# blackbox_sch.net
KiCad netlist of a schematic drawn in Altium Designer
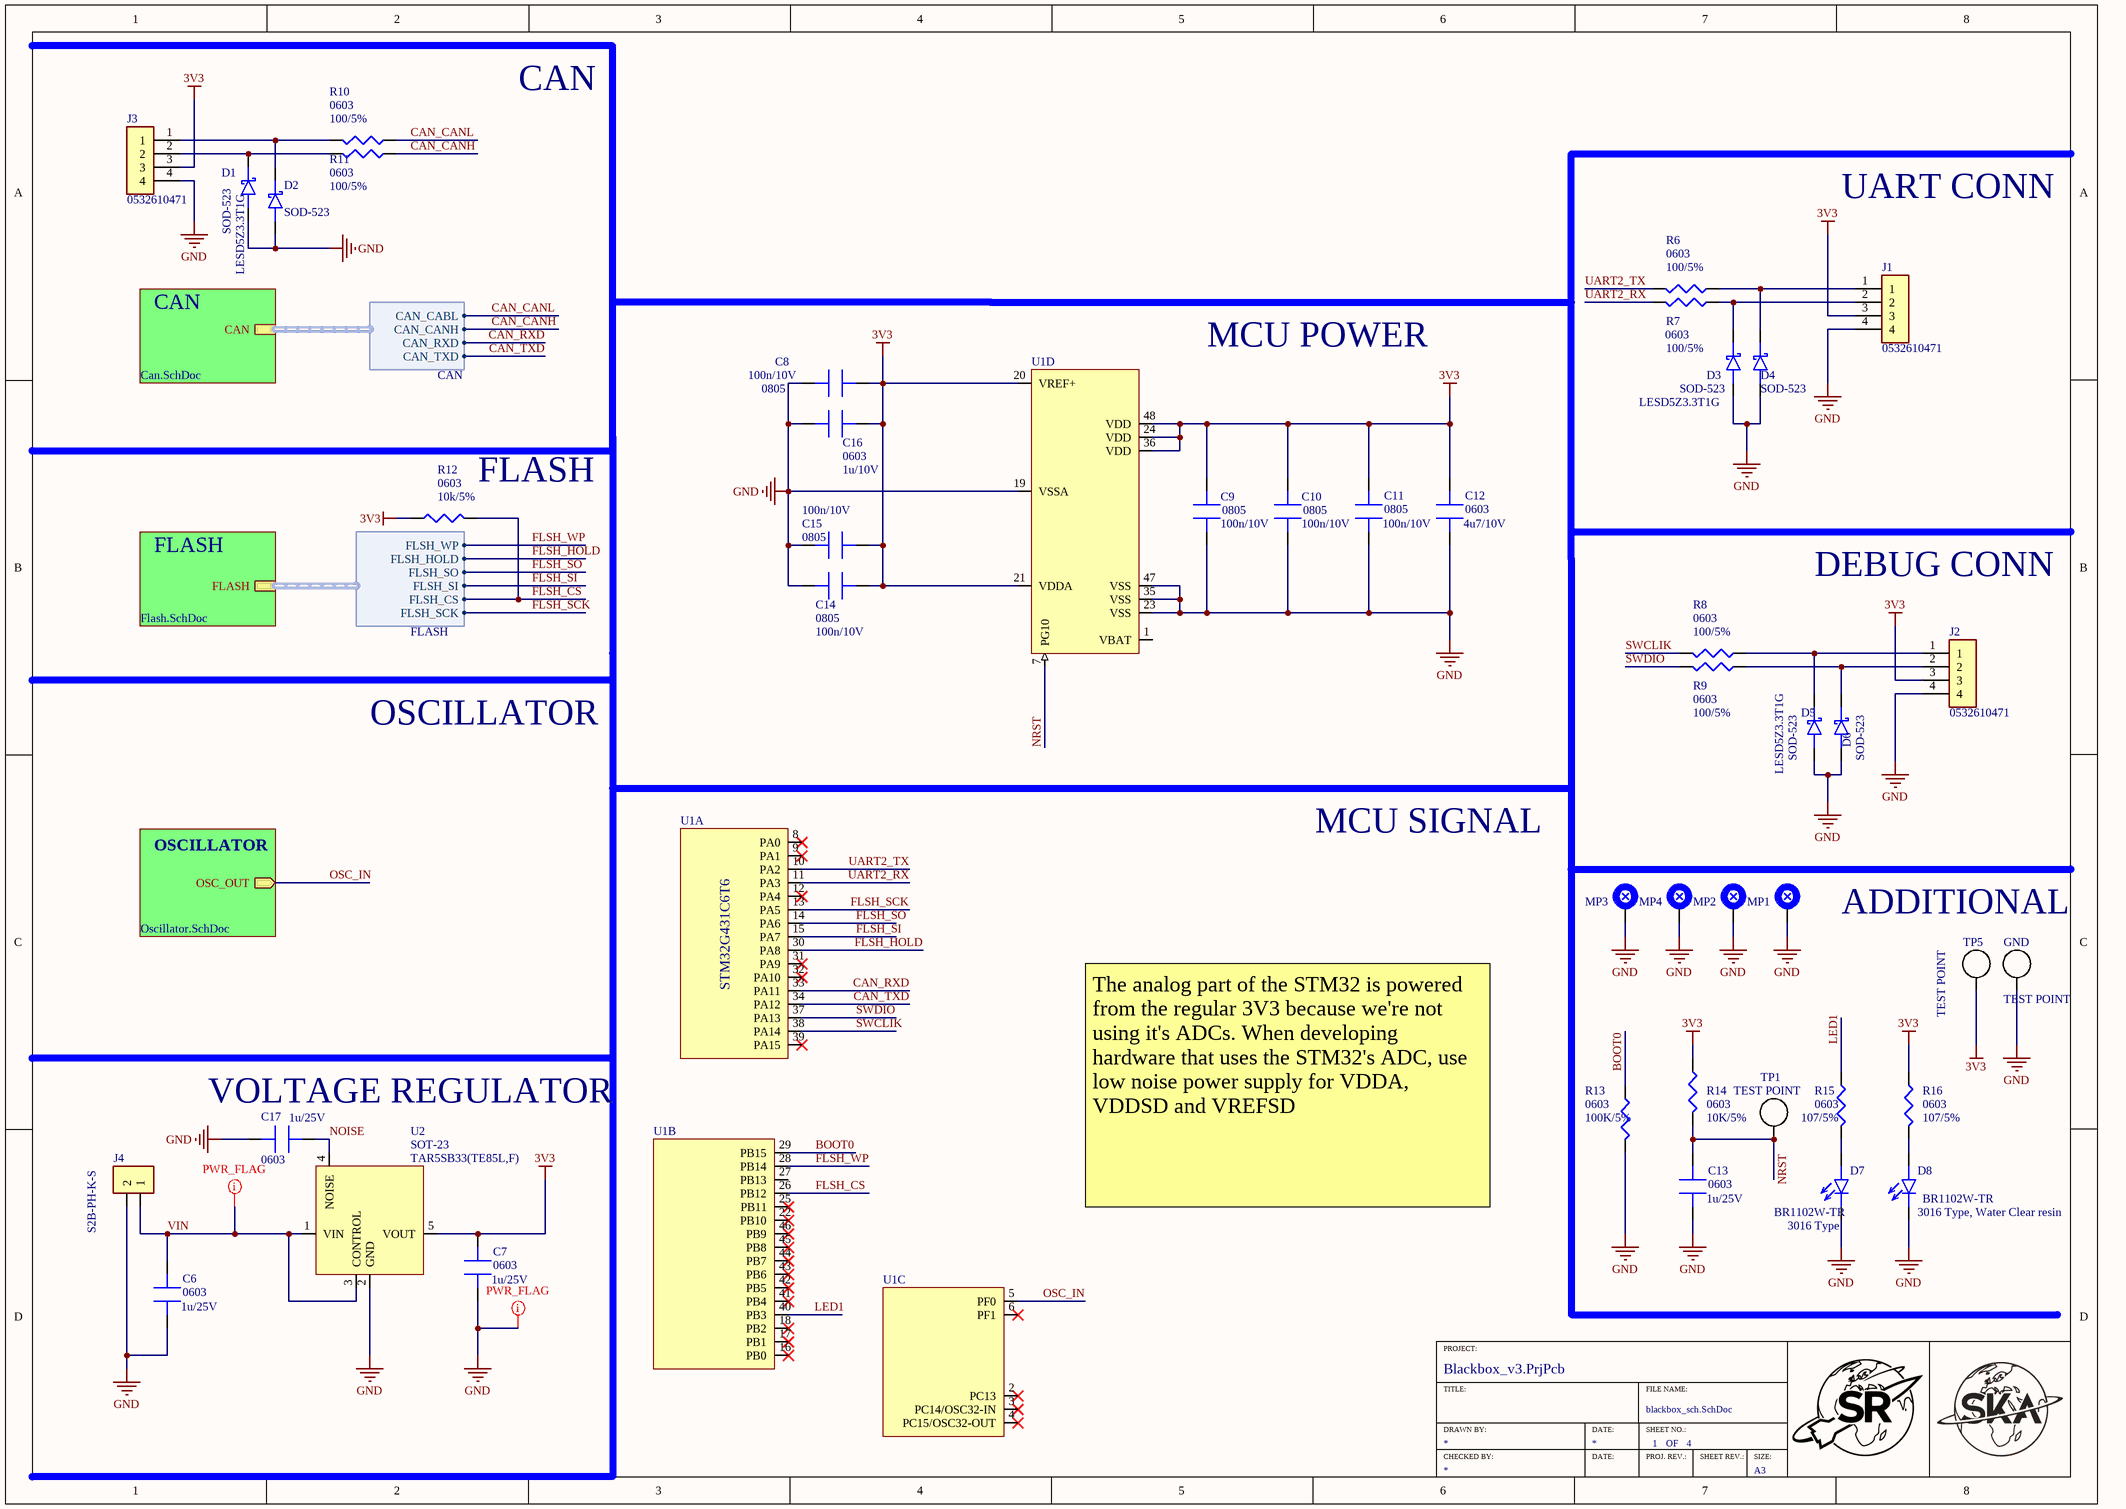
[diagram p0: blackbox_sch.SchDoc]

(export (version "E")
  (design (tool "Eeschema 10.0.6"))
  (components
    (comp (ref "C6")
      (value "1u/25V")
      (footprint "CAPC1608X10L [0603]")
      (description "Standard capacitor")
      (fields (field (name "PACKAGE") "0603") (field (name "Comment") "C"))
      (libsource (lib "SR_Library") (part "C"))
    )
    (comp (ref "C7")
      (value "1u/25V")
      (footprint "CAPC1608X10L [0603]")
      (description "Standard capacitor")
      (fields (field (name "PACKAGE") "0603") (field (name "Comment") "C"))
      (libsource (lib "SR_Library") (part "C"))
    )
    (comp (ref "C8")
      (value "100n/10V")
      (footprint "CAPC2012X09L [0805]")
      (description "Standard capacitor")
      (fields (field (name "PACKAGE") "0805") (field (name "Comment") "C"))
      (libsource (lib "SR_Library") (part "C"))
    )
    (comp (ref "C9")
      (value "100n/10V")
      (footprint "CAPC2012X09L [0805]")
      (description "Standard capacitor")
      (fields (field (name "PACKAGE") "0805") (field (name "Comment") "C"))
      (libsource (lib "SR_Library") (part "C"))
    )
    (comp (ref "C10")
      (value "100n/10V")
      (footprint "CAPC2012X09L [0805]")
      (description "Standard capacitor")
      (fields (field (name "PACKAGE") "0805") (field (name "Comment") "C"))
      (libsource (lib "SR_Library") (part "C"))
    )
    (comp (ref "C11")
      (value "100n/10V")
      (footprint "CAPC2012X09L [0805]")
      (description "Standard capacitor")
      (fields (field (name "PACKAGE") "0805") (field (name "Comment") "C"))
      (libsource (lib "SR_Library") (part "C"))
    )
    (comp (ref "C12")
      (value "4u7/10V")
      (footprint "CAPC1608X10L [0603]")
      (description "Standard capacitor")
      (fields (field (name "PACKAGE") "0603") (field (name "Comment") "C"))
      (libsource (lib "SR_Library") (part "C"))
    )
    (comp (ref "C13")
      (value "1u/25V")
      (footprint "CAPC1608X10L [0603]")
      (description "Standard capacitor")
      (fields (field (name "PACKAGE") "0603") (field (name "Comment") "C"))
      (libsource (lib "SR_Library") (part "C"))
    )
    (comp (ref "C14")
      (value "100n/10V")
      (footprint "CAPC2012X09L [0805]")
      (description "Standard capacitor")
      (fields (field (name "PACKAGE") "0805") (field (name "Comment") "C"))
      (libsource (lib "SR_Library") (part "C"))
    )
    (comp (ref "C15")
      (value "100n/10V")
      (footprint "CAPC2012X09L [0805]")
      (description "Standard capacitor")
      (fields (field (name "PACKAGE") "0805") (field (name "Comment") "C"))
      (libsource (lib "SR_Library") (part "C"))
    )
    (comp (ref "C16")
      (value "1u/10V")
      (footprint "CAPC1608X10L [0603]")
      (description "Standard capacitor")
      (fields (field (name "PACKAGE") "0603") (field (name "Comment") "C"))
      (libsource (lib "SR_Library") (part "C"))
    )
    (comp (ref "C17")
      (value "1u/25V")
      (footprint "CAPC1608X10L [0603]")
      (description "Standard capacitor")
      (fields (field (name "PACKAGE") "0603") (field (name "Comment") "C"))
      (libsource (lib "_Std_Capacitors") (part "C"))
    )
    (comp (ref "D1")
      (value "LESD5Z3.3T1G")
      (footprint "sSchottky")
      (description "Stand−off Voltage:  2.5 V −12 V \r\nPeak Power up to 200")
      (fields (field (name "PACKAGE") "SOD-523"))
      (libsource (lib "_Std_Diodes") (part "sSchottky"))
    )
    (comp (ref "D2")
      (value "LESD5Z3.3T1G")
      (footprint "sSchottky")
      (description "Stand−off Voltage:  2.5 V −12 V \r\nPeak Power up to 200")
      (fields (field (name "PACKAGE") "SOD-523"))
      (libsource (lib "_Std_Diodes") (part "sSchottky"))
    )
    (comp (ref "D3")
      (value "LESD5Z3.3T1G")
      (footprint "sSchottky")
      (description "Stand−off Voltage:  2.5 V −12 V \r\nPeak Power up to 200")
      (fields (field (name "PACKAGE") "SOD-523"))
      (libsource (lib "_Std_Diodes") (part "sSchottky"))
    )
    (comp (ref "D4")
      (value "LESD5Z3.3T1G")
      (footprint "sSchottky")
      (description "Stand−off Voltage:  2.5 V −12 V \r\nPeak Power up to 200")
      (fields (field (name "PACKAGE") "SOD-523"))
      (libsource (lib "_Std_Diodes") (part "sSchottky"))
    )
    (comp (ref "D5")
      (value "LESD5Z3.3T1G")
      (footprint "sSchottky")
      (description "Stand−off Voltage:  2.5 V −12 V \r\nPeak Power up to 200")
      (fields (field (name "PACKAGE") "SOD-523"))
      (libsource (lib "_Std_Diodes") (part "sSchottky"))
    )
    (comp (ref "D6")
      (value "LESD5Z3.3T1G")
      (footprint "sSchottky")
      (description "Stand−off Voltage:  2.5 V −12 V \r\nPeak Power up to 200")
      (fields (field (name "PACKAGE") "SOD-523"))
      (libsource (lib "_Std_Diodes") (part "sSchottky"))
    )
    (comp (ref "D7")
      (value "BR1102W-TR")
      (footprint "SODFL160X130-2N")
      (description "Standard LEDs - SMD Surface Mount LED")
      (fields (field (name "PACKAGE") "3016 Type"))
      (libsource (lib "_Std_Diodes") (part "sLED"))
    )
    (comp (ref "D8")
      (value "BR1102W-TR")
      (footprint "SODFL160X130-2N")
      (description "Standard LEDs - SMD Surface Mount LED")
      (fields
        (field (name "PACKAGE") "3016 Type, Water Clear resin")
        (field (name "SUPPLIER PART NUMBER 1") "BR1102W-TR")
      )
      (libsource (lib "_Std_Diodes") (part "sLED"))
    )
    (comp (ref "GND")
      (value "TEST POINT")
      (footprint "TEST POINT")
      (libsource (lib "_Std_Others") (part "TEST POINT"))
    )
    (comp (ref "J1")
      (value "0532610471")
      (footprint "MOLEX_0532610471")
      (description "Connector Header Surface Mount, Right Angle 4 position 0.049\" (1.25mm)")
      (libsource (lib "_Conn_Molex") (part "MOLEX_PicoBlade"))
    )
    (comp (ref "J2")
      (value "0532610471")
      (footprint "MOLEX_0532610471")
      (description "Connector Header Surface Mount, Right Angle 4 position 0.049\" (1.25mm)")
      (libsource (lib "_Conn_Molex") (part "MOLEX_PicoBlade"))
    )
    (comp (ref "J3")
      (value "0532610471")
      (footprint "MOLEX_0532610471")
      (description "Connector Header Surface Mount, Right Angle 4 position 0.049\" (1.25mm)")
      (libsource (lib "") (part "MOLEX_PicoBlade_1"))
    )
    (comp (ref "J4")
      (value "JST_PH_S2B-PH-K-S")
      (footprint "JST_PH_S2B-PH-K-S")
      (description "JST 2-pin connector, male, horizontal, pitch 2.00mm")
      (fields (field (name "PN") "S2B-PH-K-S"))
      (libsource (lib "_Conn_JST") (part "JST_PH_S2B-PH-K-S"))
    )
    (comp (ref "MP1")
      (value "Mounting hole")
      (footprint "Mounting_hole_M3")
      (libsource (lib "_Mechanical") (part "Mounting hole"))
    )
    (comp (ref "MP2")
      (value "Mounting hole")
      (footprint "Mounting_hole_M3")
      (libsource (lib "_Mechanical") (part "Mounting hole"))
    )
    (comp (ref "MP3")
      (value "Mounting hole")
      (footprint "Mounting_hole_M3")
      (libsource (lib "_Mechanical") (part "Mounting hole"))
    )
    (comp (ref "MP4")
      (value "Mounting hole")
      (footprint "Mounting_hole_M3")
      (libsource (lib "_Mechanical") (part "Mounting hole"))
    )
    (comp (ref "R6")
      (value "100/5%")
      (footprint "RESC1608X05L [0603]")
      (description "Standard resistor")
      (fields (field (name "PACKAGE") "0603") (field (name "Comment") "R"))
      (libsource (lib "SR_Library") (part "R"))
    )
    (comp (ref "R7")
      (value "100/5%")
      (footprint "RESC1608X05L [0603]")
      (description "Standard resistor")
      (fields (field (name "PACKAGE") "0603") (field (name "Comment") "R"))
      (libsource (lib "SR_Library") (part "R"))
    )
    (comp (ref "R8")
      (value "100/5%")
      (footprint "RESC1608X05L [0603]")
      (description "Standard resistor")
      (fields (field (name "PACKAGE") "0603") (field (name "Comment") "R"))
      (libsource (lib "SR_Library") (part "R"))
    )
    (comp (ref "R9")
      (value "100/5%")
      (footprint "RESC1608X05L [0603]")
      (description "Standard resistor")
      (fields (field (name "PACKAGE") "0603") (field (name "Comment") "R"))
      (libsource (lib "SR_Library") (part "R"))
    )
    (comp (ref "R10")
      (value "100/5%")
      (footprint "RESC1608X05L [0603]")
      (description "Standard resistor")
      (fields (field (name "PACKAGE") "0603") (field (name "Comment") "R"))
      (libsource (lib "SR_Library") (part "R"))
    )
    (comp (ref "R11")
      (value "100/5%")
      (footprint "RESC1608X05L [0603]")
      (description "Standard resistor")
      (fields (field (name "PACKAGE") "0603") (field (name "Comment") "R"))
      (libsource (lib "SR_Library") (part "R"))
    )
    (comp (ref "R12")
      (value "10k/5%")
      (footprint "RESC1608X05L [0603]")
      (description "Standard resistor")
      (fields (field (name "PACKAGE") "0603") (field (name "Comment") "R"))
      (libsource (lib "SR_Library") (part "R"))
    )
    (comp (ref "R13")
      (value "100K/5%")
      (footprint "RESC1608X05L [0603]")
      (description "Standard resistor")
      (fields (field (name "PACKAGE") "0603") (field (name "Comment") "R"))
      (libsource (lib "SR_Library") (part "R"))
    )
    (comp (ref "R14")
      (value "10K/5%")
      (footprint "RESC1608X05L [0603]")
      (description "Standard resistor")
      (fields (field (name "PACKAGE") "0603") (field (name "Comment") "R"))
      (libsource (lib "SR_Library") (part "R"))
    )
    (comp (ref "R15")
      (value "107/5%")
      (footprint "RESC1608X05L [0603]")
      (description "Standard resistor")
      (fields (field (name "PACKAGE") "0603") (field (name "Comment") "R"))
      (libsource (lib "SR_Library") (part "R"))
    )
    (comp (ref "R16")
      (value "107/5%")
      (footprint "RESC1608X05L [0603]")
      (description "Standard resistor")
      (fields (field (name "PACKAGE") "0603") (field (name "Comment") "R"))
      (libsource (lib "SR_Library") (part "R"))
    )
    (comp (ref "TP1")
      (value "TEST POINT")
      (footprint "TEST POINT")
      (libsource (lib "_Std_Others") (part "TEST POINT"))
    )
    (comp (ref "TP5")
      (value "TEST POINT")
      (footprint "TEST POINT")
      (libsource (lib "_Std_Others") (part "TEST POINT"))
    )
    (comp (ref "U1")
      (value "IC MCU 32BIT 32KB FLASH 48LQFP")
      (footprint "TSQFP50P900X900X160-48N")
      (libsource (lib "") (part "STM32G431C6T6_1"))
    )
    (comp (ref "U2")
      (value "LDO Voltage Regulators")
      (footprint "SOT95P275X140-5N")
      (description "LDO Voltage Regulators Point Reg SGL output 200mA 15V 3.3Vout")
      (fields (field (name "SUPPLIER PART NUMBER") "TAR5SB33(TE85L,F)") (field (name "PACLAGE") "SOT-23"))
      (libsource (lib "_IC_Power") (part "TAR5SB33(TE85L,F)"))
    )
  )
  (nets
    (net (code "3") (name "/BOOT0") (class "Default")
      (node (ref "R13") (pin "2") (pinfunction "2_2") (pintype "passive"))
      (node (ref "U1") (pin "29") (pinfunction "PB15_29") (pintype "bidirectional"))
    )
    (net (code "4") (name "/CAN_CANH") (class "Default")
      (node (ref "R11") (pin "2") (pinfunction "2_2") (pintype "passive"))
    )
    (net (code "5") (name "/CAN_CANL") (class "Default")
      (node (ref "R10") (pin "2") (pinfunction "2_2") (pintype "passive"))
    )
    (net (code "6") (name "/CAN_RXD") (class "Default")
      (node (ref "U1") (pin "33") (pinfunction "PA11_33") (pintype "bidirectional"))
    )
    (net (code "7") (name "/CAN_TXD") (class "Default")
      (node (ref "U1") (pin "34") (pinfunction "PA12_34") (pintype "bidirectional"))
    )
    (net (code "8") (name "/FLSH_CS") (class "Default")
      (node (ref "R12") (pin "1") (pinfunction "1_1") (pintype "passive"))
      (node (ref "U1") (pin "26") (pinfunction "PB12_26") (pintype "bidirectional"))
    )
    (net (code "9") (name "/FLSH_HOLD") (class "Default")
      (node (ref "U1") (pin "30") (pinfunction "PA8_30") (pintype "bidirectional"))
    )
    (net (code "10") (name "/FLSH_SCK") (class "Default")
      (node (ref "U1") (pin "13") (pinfunction "PA5_13") (pintype "bidirectional"))
    )
    (net (code "11") (name "/FLSH_SI") (class "Default")
      (node (ref "U1") (pin "15") (pinfunction "PA7_15") (pintype "bidirectional"))
    )
    (net (code "12") (name "/FLSH_SO") (class "Default")
      (node (ref "U1") (pin "14") (pinfunction "PA6_14") (pintype "bidirectional"))
    )
    (net (code "13") (name "/FLSH_WP") (class "Default")
      (node (ref "U1") (pin "28") (pinfunction "PB14_28") (pintype "bidirectional"))
    )
    (net (code "14") (name "/LED1") (class "Default")
      (node (ref "R15") (pin "2") (pinfunction "2_2") (pintype "passive"))
      (node (ref "U1") (pin "40") (pinfunction "PB3_40") (pintype "bidirectional"))
    )
    (net (code "15") (name "/NOISE") (class "Default")
      (node (ref "C17") (pin "2") (pinfunction "2_2") (pintype "passive"))
      (node (ref "U2") (pin "4") (pinfunction "NOISE_4") (pintype "passive"))
    )
    (net (code "16") (name "/NRST") (class "Default")
      (node (ref "C13") (pin "2") (pinfunction "2_2") (pintype "passive"))
      (node (ref "R14") (pin "1") (pinfunction "1_1") (pintype "passive"))
      (node (ref "TP1") (pin "1") (pinfunction "1_1") (pintype "passive"))
      (node (ref "U1") (pin "7") (pinfunction "PG10_7") (pintype "input"))
    )
    (net (code "17") (name "/OSC_IN") (class "Default")
      (node (ref "U1") (pin "5") (pinfunction "PF0_5") (pintype "bidirectional"))
    )
    (net (code "18") (name "/SWCLIK") (class "Default")
      (node (ref "R8") (pin "1") (pinfunction "1_1") (pintype "passive"))
      (node (ref "U1") (pin "38") (pinfunction "PA14_38") (pintype "bidirectional"))
    )
    (net (code "19") (name "/SWDIO") (class "Default")
      (node (ref "R9") (pin "1") (pinfunction "1_1") (pintype "passive"))
      (node (ref "U1") (pin "37") (pinfunction "PA13_37") (pintype "bidirectional"))
    )
    (net (code "20") (name "/UART2_RX") (class "Default")
      (node (ref "R7") (pin "1") (pinfunction "1_1") (pintype "passive"))
      (node (ref "U1") (pin "11") (pinfunction "PA3_11") (pintype "bidirectional"))
    )
    (net (code "21") (name "/UART2_TX") (class "Default")
      (node (ref "R6") (pin "1") (pinfunction "1_1") (pintype "passive"))
      (node (ref "U1") (pin "10") (pinfunction "PA2_10") (pintype "bidirectional"))
    )
    (net (code "22") (name "/VIN") (class "Default")
      (node (ref "C6") (pin "2") (pinfunction "2_2") (pintype "passive"))
      (node (ref "J4") (pin "1") (pinfunction "1_1") (pintype "passive"))
      (node (ref "U2") (pin "1") (pinfunction "VIN_1") (pintype "passive"))
      (node (ref "U2") (pin "3") (pinfunction "CONTROL_3") (pintype "passive"))
    )
    (net (code "25") (name "3V3") (class "Default")
      (node (ref "C10") (pin "2") (pinfunction "2_2") (pintype "passive"))
      (node (ref "C11") (pin "2") (pinfunction "2_2") (pintype "passive"))
      (node (ref "C12") (pin "2") (pinfunction "2_2") (pintype "passive"))
      (node (ref "C14") (pin "1") (pinfunction "1_1") (pintype "passive"))
      (node (ref "C15") (pin "1") (pinfunction "1_1") (pintype "passive"))
      (node (ref "C16") (pin "2") (pinfunction "2_2") (pintype "passive"))
      (node (ref "C7") (pin "2") (pinfunction "2_2") (pintype "passive"))
      (node (ref "C8") (pin "2") (pinfunction "2_2") (pintype "passive"))
      (node (ref "C9") (pin "2") (pinfunction "2_2") (pintype "passive"))
      (node (ref "J1") (pin "3") (pinfunction "3_3") (pintype "passive"))
      (node (ref "J2") (pin "3") (pinfunction "3_3") (pintype "passive"))
      (node (ref "J3") (pin "3") (pinfunction "3_3") (pintype "passive"))
      (node (ref "R12") (pin "2") (pinfunction "2_2") (pintype "passive"))
      (node (ref "R14") (pin "2") (pinfunction "2_2") (pintype "passive"))
      (node (ref "R16") (pin "2") (pinfunction "2_2") (pintype "passive"))
      (node (ref "TP5") (pin "1") (pinfunction "1_1") (pintype "passive"))
      (node (ref "U1") (pin "20") (pinfunction "VREF+_20") (pintype "power_in"))
      (node (ref "U1") (pin "21") (pinfunction "VDDA_21") (pintype "power_in"))
      (node (ref "U1") (pin "24") (pinfunction "VDD_24") (pintype "power_in"))
      (node (ref "U1") (pin "36") (pinfunction "VDD_36") (pintype "power_in"))
      (node (ref "U1") (pin "48") (pinfunction "VDD_48") (pintype "power_in"))
      (node (ref "U2") (pin "5") (pinfunction "VOUT_5") (pintype "passive"))
    )
    (net (code "26") (name "GND") (class "Default")
      (node (ref "C10") (pin "1") (pinfunction "1_1") (pintype "passive"))
      (node (ref "C11") (pin "1") (pinfunction "1_1") (pintype "passive"))
      (node (ref "C12") (pin "1") (pinfunction "1_1") (pintype "passive"))
      (node (ref "C13") (pin "1") (pinfunction "1_1") (pintype "passive"))
      (node (ref "C14") (pin "2") (pinfunction "2_2") (pintype "passive"))
      (node (ref "C15") (pin "2") (pinfunction "2_2") (pintype "passive"))
      (node (ref "C16") (pin "1") (pinfunction "1_1") (pintype "passive"))
      (node (ref "C17") (pin "1") (pinfunction "1_1") (pintype "passive"))
      (node (ref "C6") (pin "1") (pinfunction "1_1") (pintype "passive"))
      (node (ref "C7") (pin "1") (pinfunction "1_1") (pintype "passive"))
      (node (ref "C8") (pin "1") (pinfunction "1_1") (pintype "passive"))
      (node (ref "C9") (pin "1") (pinfunction "1_1") (pintype "passive"))
      (node (ref "D1") (pin "2") (pinfunction "2_2") (pintype "passive"))
      (node (ref "D2") (pin "2") (pinfunction "2_2") (pintype "passive"))
      (node (ref "D3") (pin "2") (pinfunction "2_2") (pintype "passive"))
      (node (ref "D4") (pin "2") (pinfunction "2_2") (pintype "passive"))
      (node (ref "D5") (pin "2") (pinfunction "2_2") (pintype "passive"))
      (node (ref "D6") (pin "2") (pinfunction "2_2") (pintype "passive"))
      (node (ref "D7") (pin "1") (pinfunction "1_1") (pintype "passive"))
      (node (ref "D8") (pin "1") (pinfunction "1_1") (pintype "passive"))
      (node (ref "GND") (pin "1") (pinfunction "1_1") (pintype "passive"))
      (node (ref "J1") (pin "4") (pinfunction "4_4") (pintype "passive"))
      (node (ref "J2") (pin "4") (pinfunction "4_4") (pintype "passive"))
      (node (ref "J3") (pin "4") (pinfunction "4_4") (pintype "passive"))
      (node (ref "J4") (pin "2") (pinfunction "2_2") (pintype "passive"))
      (node (ref "MP1") (pin "1") (pinfunction "1_1") (pintype "passive"))
      (node (ref "MP2") (pin "1") (pinfunction "1_1") (pintype "passive"))
      (node (ref "MP3") (pin "1") (pinfunction "1_1") (pintype "passive"))
      (node (ref "MP4") (pin "1") (pinfunction "1_1") (pintype "passive"))
      (node (ref "R13") (pin "1") (pinfunction "1_1") (pintype "passive"))
      (node (ref "U1") (pin "19") (pinfunction "VSSA_19") (pintype "power_in"))
      (node (ref "U1") (pin "23") (pinfunction "VSS_23") (pintype "power_in"))
      (node (ref "U1") (pin "35") (pinfunction "VSS_35") (pintype "power_in"))
      (node (ref "U1") (pin "47") (pinfunction "VSS_47") (pintype "power_in"))
      (node (ref "U2") (pin "2") (pinfunction "GND_2") (pintype "passive"))
    )
    (net (code "27") (name "Net-(D1-Pad1)") (class "Default")
      (node (ref "D1") (pin "1") (pinfunction "1_1") (pintype "passive"))
      (node (ref "J3") (pin "2") (pinfunction "2_2") (pintype "passive"))
      (node (ref "R11") (pin "1") (pinfunction "1_1") (pintype "passive"))
    )
    (net (code "28") (name "Net-(D2-Pad1)") (class "Default")
      (node (ref "D2") (pin "1") (pinfunction "1_1") (pintype "passive"))
      (node (ref "J3") (pin "1") (pinfunction "1_1") (pintype "passive"))
      (node (ref "R10") (pin "1") (pinfunction "1_1") (pintype "passive"))
    )
    (net (code "29") (name "Net-(D3-Pad1)") (class "Default")
      (node (ref "D3") (pin "1") (pinfunction "1_1") (pintype "passive"))
      (node (ref "J1") (pin "2") (pinfunction "2_2") (pintype "passive"))
      (node (ref "R7") (pin "2") (pinfunction "2_2") (pintype "passive"))
    )
    (net (code "30") (name "Net-(D4-Pad1)") (class "Default")
      (node (ref "D4") (pin "1") (pinfunction "1_1") (pintype "passive"))
      (node (ref "J1") (pin "1") (pinfunction "1_1") (pintype "passive"))
      (node (ref "R6") (pin "2") (pinfunction "2_2") (pintype "passive"))
    )
    (net (code "31") (name "Net-(D5-Pad1)") (class "Default")
      (node (ref "D5") (pin "1") (pinfunction "1_1") (pintype "passive"))
      (node (ref "J2") (pin "1") (pinfunction "1_1") (pintype "passive"))
      (node (ref "R8") (pin "2") (pinfunction "2_2") (pintype "passive"))
    )
    (net (code "32") (name "Net-(D6-Pad1)") (class "Default")
      (node (ref "D6") (pin "1") (pinfunction "1_1") (pintype "passive"))
      (node (ref "J2") (pin "2") (pinfunction "2_2") (pintype "passive"))
      (node (ref "R9") (pin "2") (pinfunction "2_2") (pintype "passive"))
    )
    (net (code "33") (name "Net-(D7-Pad2)") (class "Default")
      (node (ref "D7") (pin "2") (pinfunction "2_2") (pintype "passive"))
      (node (ref "R15") (pin "1") (pinfunction "1_1") (pintype "passive"))
    )
    (net (code "34") (name "Net-(D8-Pad2)") (class "Default")
      (node (ref "D8") (pin "2") (pinfunction "2_2") (pintype "passive"))
      (node (ref "R16") (pin "1") (pinfunction "1_1") (pintype "passive"))
    )
    (net (code "35") (name "unconnected-(U1A-PA0-Pad8)") (class "Default")
      (node (ref "U1") (pin "8") (pinfunction "PA0_8") (pintype "bidirectional+no_connect"))
    )
    (net (code "36") (name "unconnected-(U1A-PA1-Pad9)") (class "Default")
      (node (ref "U1") (pin "9") (pinfunction "PA1_9") (pintype "bidirectional+no_connect"))
    )
    (net (code "37") (name "unconnected-(U1A-PA4-Pad12)") (class "Default")
      (node (ref "U1") (pin "12") (pinfunction "PA4_12") (pintype "bidirectional+no_connect"))
    )
    (net (code "38") (name "unconnected-(U1A-PA9-Pad31)") (class "Default")
      (node (ref "U1") (pin "31") (pinfunction "PA9_31") (pintype "bidirectional+no_connect"))
    )
    (net (code "39") (name "unconnected-(U1A-PA10-Pad32)") (class "Default")
      (node (ref "U1") (pin "32") (pinfunction "PA10_32") (pintype "bidirectional+no_connect"))
    )
    (net (code "40") (name "unconnected-(U1A-PA15-Pad39)") (class "Default")
      (node (ref "U1") (pin "39") (pinfunction "PA15_39") (pintype "bidirectional+no_connect"))
    )
    (net (code "41") (name "unconnected-(U1B-PB0-Pad16)") (class "Default")
      (node (ref "U1") (pin "16") (pinfunction "PB0_16") (pintype "bidirectional+no_connect"))
    )
    (net (code "42") (name "unconnected-(U1B-PB1-Pad17)") (class "Default")
      (node (ref "U1") (pin "17") (pinfunction "PB1_17") (pintype "bidirectional+no_connect"))
    )
    (net (code "43") (name "unconnected-(U1B-PB2-Pad18)") (class "Default")
      (node (ref "U1") (pin "18") (pinfunction "PB2_18") (pintype "bidirectional+no_connect"))
    )
    (net (code "44") (name "unconnected-(U1B-PB4-Pad41)") (class "Default")
      (node (ref "U1") (pin "41") (pinfunction "PB4_41") (pintype "bidirectional+no_connect"))
    )
    (net (code "45") (name "unconnected-(U1B-PB5-Pad42)") (class "Default")
      (node (ref "U1") (pin "42") (pinfunction "PB5_42") (pintype "bidirectional+no_connect"))
    )
    (net (code "46") (name "unconnected-(U1B-PB6-Pad43)") (class "Default")
      (node (ref "U1") (pin "43") (pinfunction "PB6_43") (pintype "bidirectional+no_connect"))
    )
    (net (code "47") (name "unconnected-(U1B-PB7-Pad44)") (class "Default")
      (node (ref "U1") (pin "44") (pinfunction "PB7_44") (pintype "bidirectional+no_connect"))
    )
    (net (code "48") (name "unconnected-(U1B-PB8-Pad45)") (class "Default")
      (node (ref "U1") (pin "45") (pinfunction "PB8_45") (pintype "bidirectional+no_connect"))
    )
    (net (code "49") (name "unconnected-(U1B-PB9-Pad46)") (class "Default")
      (node (ref "U1") (pin "46") (pinfunction "PB9_46") (pintype "bidirectional+no_connect"))
    )
    (net (code "50") (name "unconnected-(U1B-PB10-Pad22)") (class "Default")
      (node (ref "U1") (pin "22") (pinfunction "PB10_22") (pintype "bidirectional+no_connect"))
    )
    (net (code "51") (name "unconnected-(U1B-PB11-Pad25)") (class "Default")
      (node (ref "U1") (pin "25") (pinfunction "PB11_25") (pintype "bidirectional+no_connect"))
    )
    (net (code "52") (name "unconnected-(U1B-PB13-Pad27)") (class "Default")
      (node (ref "U1") (pin "27") (pinfunction "PB13_27") (pintype "bidirectional"))
    )
    (net (code "53") (name "unconnected-(U1C-PC13-Pad2)") (class "Default")
      (node (ref "U1") (pin "2") (pinfunction "PC13_2") (pintype "bidirectional+no_connect"))
    )
    (net (code "54") (name "unconnected-(U1C-PC14{slash}OSC32-IN-Pad3)") (class "Default")
      (node (ref "U1") (pin "3") (pinfunction "PC14/OSC32-IN_3") (pintype "bidirectional+no_connect"))
    )
    (net (code "55") (name "unconnected-(U1C-PC15{slash}OSC32-OUT-Pad4)") (class "Default")
      (node (ref "U1") (pin "4") (pinfunction "PC15/OSC32-OUT_4") (pintype "bidirectional+no_connect"))
    )
    (net (code "56") (name "unconnected-(U1C-PF1-Pad6)") (class "Default")
      (node (ref "U1") (pin "6") (pinfunction "PF1_6") (pintype "bidirectional+no_connect"))
    )
    (net (code "57") (name "unconnected-(U1D-VBAT-Pad1)") (class "Default")
      (node (ref "U1") (pin "1") (pinfunction "VBAT_1") (pintype "power_in"))
    )
  )
)
